# 300mV_Reference_Voltage.net
KiCad netlist of a schematic drawn in Altium Designer
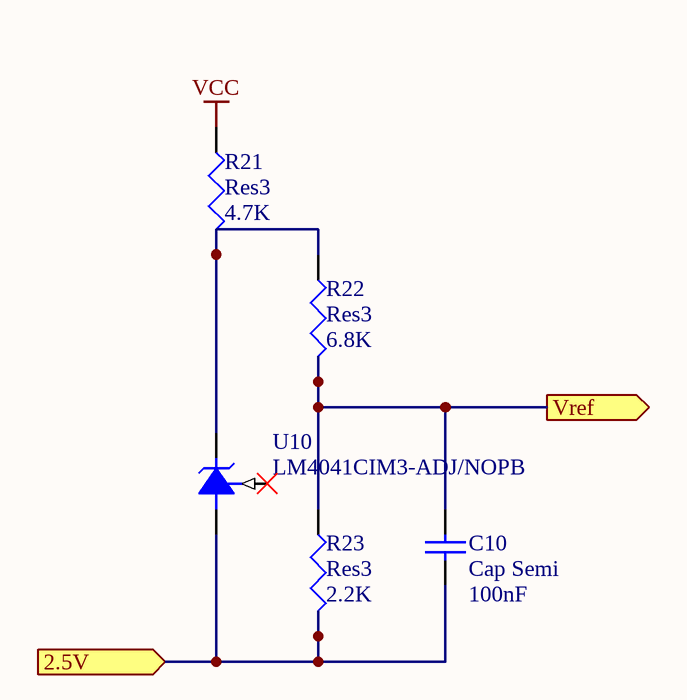
[diagram p0: 300mV_Reference_Voltage.SchDoc]

(export (version "E")
  (design (tool "Eeschema 10.0.6"))
  (components
    (comp (ref "C10")
      (value "Cap Semi")
      (footprint "C1206")
      (description "Capacitor (Semiconductor SIM Model)")
      (fields (field (name "ALTIUM_VALUE") "100nF") (field (name "PUBLISHER") "Altium Limited"))
      (libsource (lib "Miscellaneous Devices") (part "Cap Semi"))
    )
    (comp (ref "R21")
      (value "Res3")
      (footprint "J1-0603")
      (description "Resistor")
      (fields (field (name "ALTIUM_VALUE") "4.7K") (field (name "PUBLISHER") "Altium Limited"))
      (libsource (lib "Miscellaneous Devices") (part "Res3"))
    )
    (comp (ref "R22")
      (value "Res3")
      (footprint "J1-0603")
      (description "Resistor")
      (fields (field (name "ALTIUM_VALUE") "6.8K") (field (name "PUBLISHER") "Altium Limited"))
      (libsource (lib "Miscellaneous Devices") (part "Res3"))
    )
    (comp (ref "R23")
      (value "Res3")
      (footprint "J1-0603")
      (description "Resistor")
      (fields (field (name "ALTIUM_VALUE") "2.2K") (field (name "PUBLISHER") "Altium Limited"))
      (libsource (lib "Miscellaneous Devices") (part "Res3"))
    )
    (comp (ref "U10")
      (value "LM4041CIM3-ADJ/NOPB")
      (footprint "MF03A_M")
      (description "Precision Micropower Shunt Voltage Reference, 3-pin SOT-23, Pb-Free")
      (fields (field (name "MANUFACTURER") "National Semiconductor"))
      (libsource (lib "Altium Content Vault") (part "PM-REF-LM113FB-3"))
    )
  )
  (nets
    (net (code "1") (name "/2.5V") (class "Default")
      (node (ref "C10") (pin "1") (pinfunction "1_1") (pintype "passive"))
      (node (ref "R23") (pin "2") (pinfunction "2_2") (pintype "passive"))
      (node (ref "U10") (pin "3") (pinfunction "-V_3") (pintype "passive"))
    )
    (net (code "2") (name "/Vref") (class "Default")
      (node (ref "C10") (pin "2") (pinfunction "2_2") (pintype "passive"))
      (node (ref "R22") (pin "2") (pinfunction "2_2") (pintype "passive"))
      (node (ref "R23") (pin "1") (pinfunction "1_1") (pintype "passive"))
    )
    (net (code "3") (name "Net-(U10-+V)") (class "Default")
      (node (ref "R21") (pin "2") (pinfunction "2_2") (pintype "passive"))
      (node (ref "R22") (pin "1") (pinfunction "1_1") (pintype "passive"))
      (node (ref "U10") (pin "2") (pinfunction "+V_2") (pintype "passive"))
    )
    (net (code "4") (name "VCC") (class "Default")
      (node (ref "R21") (pin "1") (pinfunction "1_1") (pintype "passive"))
    )
    (net (code "5") (name "unconnected-(U10-FB-Pad1)") (class "Default")
      (node (ref "U10") (pin "1") (pinfunction "FB_1") (pintype "input+no_connect"))
    )
  )
)
